# SCH_06_Input.net
KiCad netlist of a schematic drawn in Altium Designer
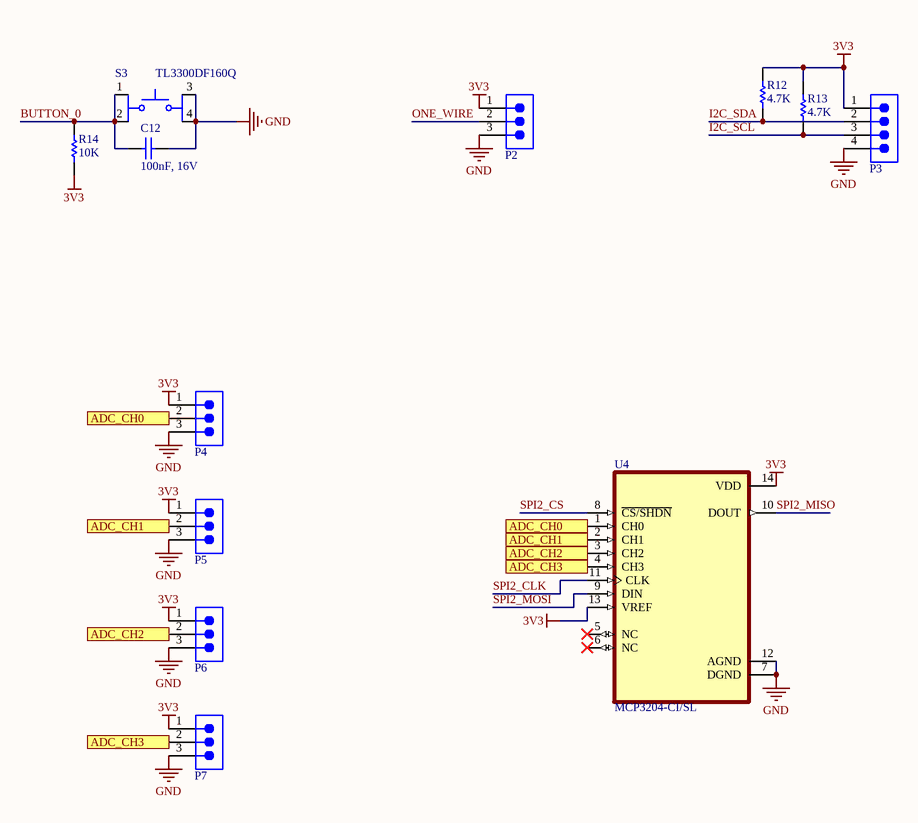
[diagram p0: SCH_06_Input.SchDoc]

(export (version "E")
  (design (tool "Eeschema 10.0.6"))
  (components
    (comp (ref "C12")
      (value "100nF, 16V")
      (footprint "WCAP-CSGP_0603_H=0.8mm_Reflow")
      (description "WCAP-CSGP Multilayer Ceramic Chip Capacitor, General Purpose, size 0603, X7R, 100nF, 16V")
      (fields
        (field (name "MANUFACTURER PART NUMBER") "885012206046")
        (field (name "MANUFACTURER") "Wurth Elektronik")
      )
      (libsource (lib "Altium_WCAP-CSGP (rev20a)") (part "885012206046"))
    )
    (comp (ref "P2")
      (value "691312510003")
      (footprint "691312510003")
      (description "WR-TBL Series 312 Open Horizontal PCB Header, THT, pitch 5.08mm, 3p")
      (fields (field (name "MANUFACTURER") "Wurth Elektronik"))
      (libsource (lib "Altium_WR-TBL (rev22b)") (part "691312510003"))
    )
    (comp (ref "P3")
      (value "691312510004")
      (footprint "691312510004")
      (description "WR-TBL Series 312 Open Horizontal PCB Header, THT, pitch 5.08mm, 4p")
      (fields (field (name "MANUFACTURER") "Wurth Elektronik"))
      (libsource (lib "Altium_WR-TBL (rev22b)") (part "691312510004"))
    )
    (comp (ref "P4")
      (value "691312510003")
      (footprint "691312510003")
      (description "WR-TBL Series 312 Open Horizontal PCB Header, THT, pitch 5.08mm, 3p")
      (fields (field (name "MANUFACTURER") "Wurth Elektronik"))
      (libsource (lib "Altium_WR-TBL (rev22b)") (part "691312510003"))
    )
    (comp (ref "P5")
      (value "691312510003")
      (footprint "691312510003")
      (description "WR-TBL Series 312 Open Horizontal PCB Header, THT, pitch 5.08mm, 3p")
      (fields (field (name "MANUFACTURER") "Wurth Elektronik"))
      (libsource (lib "Altium_WR-TBL (rev22b)") (part "691312510003"))
    )
    (comp (ref "P6")
      (value "691312510003")
      (footprint "691312510003")
      (description "WR-TBL Series 312 Open Horizontal PCB Header, THT, pitch 5.08mm, 3p")
      (fields (field (name "MANUFACTURER") "Wurth Elektronik"))
      (libsource (lib "Altium_WR-TBL (rev22b)") (part "691312510003"))
    )
    (comp (ref "P7")
      (value "691312510003")
      (footprint "691312510003")
      (description "WR-TBL Series 312 Open Horizontal PCB Header, THT, pitch 5.08mm, 3p")
      (fields (field (name "MANUFACTURER") "Wurth Elektronik"))
      (libsource (lib "Altium_WR-TBL (rev22b)") (part "691312510003"))
    )
    (comp (ref "R12")
      (value "4.7K")
      (footprint "RES-SM-0603")
      (description "Resistor")
      (fields (field (name "Comment") "RESISTOR SMD"))
      (libsource (lib "PIF_Library") (part "RESISTOR SMD"))
    )
    (comp (ref "R13")
      (value "4.7K")
      (footprint "RES-SM-0603")
      (description "Resistor")
      (fields (field (name "Comment") "RESISTOR SMD"))
      (libsource (lib "PIF_Library") (part "RESISTOR SMD"))
    )
    (comp (ref "R14")
      (value "10K")
      (footprint "RES-SM-0603")
      (description "Resistor")
      (fields (field (name "Comment") "RESISTOR SMD"))
      (libsource (lib "PIF_Library") (part "RESISTOR SMD"))
    )
    (comp (ref "S3")
      (value "TL3300DF160Q")
      (footprint "SW_TL3300DF160Q")
      (libsource (lib "Button_4_Pin_SMD") (part "TL3300DF160Q"))
    )
    (comp (ref "U4")
      (value "MCP3204-CI/SL")
      (footprint "SOIC127P600X175-14N")
      (description "12 Bit Analog to Digital Converter 2, 4 Input 1 SAR 14-SOIC")
      (fields (field (name "MF") "Microchip"))
      (libsource (lib "MCP3204-CI_SL") (part "MCP3204-CI/SL"))
    )
  )
  (nets
    (net (code "1") (name "/ADC_CH0") (class "Default")
      (node (ref "P4") (pin "2") (pinfunction "2_2") (pintype "passive"))
      (node (ref "U4") (pin "1") (pinfunction "CH0_1") (pintype "input"))
    )
    (net (code "2") (name "/ADC_CH1") (class "Default")
      (node (ref "P5") (pin "2") (pinfunction "2_2") (pintype "passive"))
      (node (ref "U4") (pin "2") (pinfunction "CH1_2") (pintype "input"))
    )
    (net (code "3") (name "/ADC_CH2") (class "Default")
      (node (ref "P6") (pin "2") (pinfunction "2_2") (pintype "passive"))
      (node (ref "U4") (pin "3") (pinfunction "CH2_3") (pintype "input"))
    )
    (net (code "4") (name "/ADC_CH3") (class "Default")
      (node (ref "P7") (pin "2") (pinfunction "2_2") (pintype "passive"))
      (node (ref "U4") (pin "4") (pinfunction "CH3_4") (pintype "input"))
    )
    (net (code "5") (name "/BUTTON_0") (class "Default")
      (node (ref "C12") (pin "2") (pinfunction "2_2") (pintype "passive"))
      (node (ref "R14") (pin "1") (pinfunction "1_1") (pintype "passive"))
      (node (ref "S3") (pin "1") (pinfunction "1_1") (pintype "passive"))
      (node (ref "S3") (pin "2") (pinfunction "2_2") (pintype "passive"))
    )
    (net (code "6") (name "/I2C_SCL") (class "Default")
      (node (ref "P3") (pin "3") (pinfunction "3_3") (pintype "passive"))
      (node (ref "R13") (pin "1") (pinfunction "1_1") (pintype "passive"))
    )
    (net (code "7") (name "/I2C_SDA") (class "Default")
      (node (ref "P3") (pin "2") (pinfunction "2_2") (pintype "passive"))
      (node (ref "R12") (pin "1") (pinfunction "1_1") (pintype "passive"))
    )
    (net (code "8") (name "/ONE_WIRE") (class "Default")
      (node (ref "P2") (pin "2") (pinfunction "2_2") (pintype "passive"))
    )
    (net (code "9") (name "/SPI2_CLK") (class "Default")
      (node (ref "U4") (pin "11") (pinfunction "CLK_11") (pintype "input"))
    )
    (net (code "10") (name "/SPI2_CS") (class "Default")
      (node (ref "U4") (pin "8") (pinfunction "~{CS/SHDN}_8") (pintype "input"))
    )
    (net (code "11") (name "/SPI2_MISO") (class "Default")
      (node (ref "U4") (pin "10") (pinfunction "DOUT_10") (pintype "output"))
    )
    (net (code "12") (name "/SPI2_MOSI") (class "Default")
      (node (ref "U4") (pin "9") (pinfunction "DIN_9") (pintype "input"))
    )
    (net (code "13") (name "3V3") (class "Default")
      (node (ref "P2") (pin "1") (pinfunction "1_1") (pintype "passive"))
      (node (ref "P3") (pin "1") (pinfunction "1_1") (pintype "passive"))
      (node (ref "P4") (pin "1") (pinfunction "1_1") (pintype "passive"))
      (node (ref "P5") (pin "1") (pinfunction "1_1") (pintype "passive"))
      (node (ref "P6") (pin "1") (pinfunction "1_1") (pintype "passive"))
      (node (ref "P7") (pin "1") (pinfunction "1_1") (pintype "passive"))
      (node (ref "R12") (pin "2") (pinfunction "2_2") (pintype "passive"))
      (node (ref "R13") (pin "2") (pinfunction "2_2") (pintype "passive"))
      (node (ref "R14") (pin "2") (pinfunction "2_2") (pintype "passive"))
      (node (ref "U4") (pin "13") (pinfunction "VREF_13") (pintype "input"))
      (node (ref "U4") (pin "14") (pinfunction "VDD_14") (pintype "power_in"))
    )
    (net (code "14") (name "GND") (class "Default")
      (node (ref "C12") (pin "1") (pinfunction "1_1") (pintype "passive"))
      (node (ref "P2") (pin "3") (pinfunction "3_3") (pintype "passive"))
      (node (ref "P3") (pin "4") (pinfunction "4_4") (pintype "passive"))
      (node (ref "P4") (pin "3") (pinfunction "3_3") (pintype "passive"))
      (node (ref "P5") (pin "3") (pinfunction "3_3") (pintype "passive"))
      (node (ref "P6") (pin "3") (pinfunction "3_3") (pintype "passive"))
      (node (ref "P7") (pin "3") (pinfunction "3_3") (pintype "passive"))
      (node (ref "S3") (pin "3") (pinfunction "3_3") (pintype "passive"))
      (node (ref "S3") (pin "4") (pinfunction "4_4") (pintype "passive"))
      (node (ref "U4") (pin "12") (pinfunction "AGND_12") (pintype "power_in"))
      (node (ref "U4") (pin "7") (pinfunction "DGND_7") (pintype "power_in"))
    )
    (net (code "15") (name "unconnected-(U4-NC-Pad5)") (class "Default")
      (node (ref "U4") (pin "5") (pinfunction "NC_5") (pintype "bidirectional+no_connect"))
    )
    (net (code "16") (name "unconnected-(U4-NC-Pad6)") (class "Default")
      (node (ref "U4") (pin "6") (pinfunction "NC_6") (pintype "bidirectional+no_connect"))
    )
  )
)
